# V1.net
KiCad netlist of a schematic drawn in EAGLE
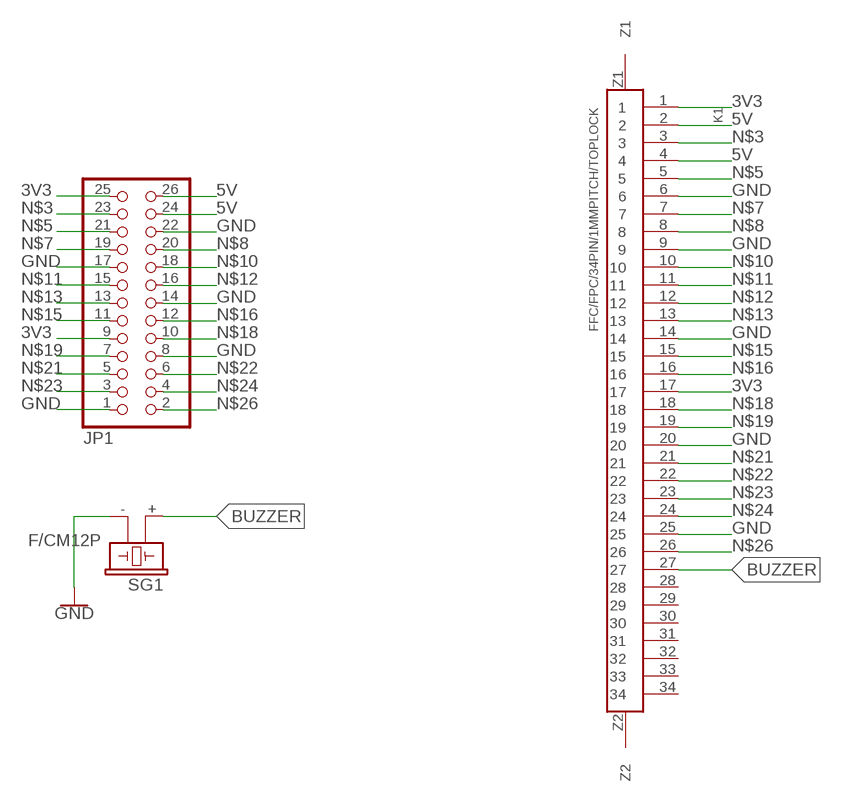
[diagram p0: schematic, sheet 1]

(export (version "E")
  (design (tool "Eeschema 10.0.6"))
  (components
    (comp (ref "JP1")
      (value "PINHD-2X13")
      (footprint "eagle-import:2X13")
      (libsource (lib "eagle-import") (part "PINHD-2X13"))
    )
    (comp (ref "K1")
      (value "FFC/FPC/34PIN/1MMPITCH/TOPLOCK")
      (footprint "eagle-import:FFC_FPC_34PIN_1MMPITCH_TOPLOCK")
      (libsource (lib "eagle-import") (part "FFC/FPC/34PIN/1MMPITCH/TOPLOCK"))
    )
    (comp (ref "SG1")
      (value "F/CM12P")
      (footprint "eagle-import:F_CM12P")
      (libsource (lib "eagle-import") (part "F/CM12P"))
    )
  )
  (nets
    (net (code "1") (name "/3V3") (class "Default")
      (node (ref "JP1") (pin "25") (pinfunction "25_25") (pintype "passive"))
      (node (ref "JP1") (pin "9") (pinfunction "9_9") (pintype "passive"))
      (node (ref "K1") (pin "1") (pinfunction "1_1") (pintype "bidirectional"))
      (node (ref "K1") (pin "17") (pinfunction "17_17") (pintype "bidirectional"))
    )
    (net (code "2") (name "/5V") (class "Default")
      (node (ref "JP1") (pin "24") (pinfunction "24_24") (pintype "passive"))
      (node (ref "JP1") (pin "26") (pinfunction "26_26") (pintype "passive"))
      (node (ref "K1") (pin "2") (pinfunction "2_2") (pintype "bidirectional"))
      (node (ref "K1") (pin "4") (pinfunction "4_4") (pintype "bidirectional"))
    )
    (net (code "3") (name "/N$3") (class "Default")
      (node (ref "JP1") (pin "23") (pinfunction "23_23") (pintype "passive"))
      (node (ref "K1") (pin "3") (pinfunction "3_3") (pintype "bidirectional"))
    )
    (net (code "4") (name "/N$5") (class "Default")
      (node (ref "JP1") (pin "21") (pinfunction "21_21") (pintype "passive"))
      (node (ref "K1") (pin "5") (pinfunction "5_5") (pintype "bidirectional"))
    )
    (net (code "5") (name "/N$7") (class "Default")
      (node (ref "JP1") (pin "19") (pinfunction "19_19") (pintype "passive"))
      (node (ref "K1") (pin "7") (pinfunction "7_7") (pintype "bidirectional"))
    )
    (net (code "6") (name "/N$8") (class "Default")
      (node (ref "JP1") (pin "20") (pinfunction "20_20") (pintype "passive"))
      (node (ref "K1") (pin "8") (pinfunction "8_8") (pintype "bidirectional"))
    )
    (net (code "7") (name "/N$10") (class "Default")
      (node (ref "JP1") (pin "18") (pinfunction "18_18") (pintype "passive"))
      (node (ref "K1") (pin "10") (pinfunction "10_10") (pintype "bidirectional"))
    )
    (net (code "8") (name "/N$11") (class "Default")
      (node (ref "JP1") (pin "15") (pinfunction "15_15") (pintype "passive"))
      (node (ref "K1") (pin "11") (pinfunction "11_11") (pintype "bidirectional"))
    )
    (net (code "9") (name "/N$12") (class "Default")
      (node (ref "JP1") (pin "16") (pinfunction "16_16") (pintype "passive"))
      (node (ref "K1") (pin "12") (pinfunction "12_12") (pintype "bidirectional"))
    )
    (net (code "10") (name "/N$13") (class "Default")
      (node (ref "JP1") (pin "13") (pinfunction "13_13") (pintype "passive"))
      (node (ref "K1") (pin "13") (pinfunction "13_13") (pintype "bidirectional"))
    )
    (net (code "11") (name "/N$15") (class "Default")
      (node (ref "JP1") (pin "11") (pinfunction "11_11") (pintype "passive"))
      (node (ref "K1") (pin "15") (pinfunction "15_15") (pintype "bidirectional"))
    )
    (net (code "12") (name "/N$16") (class "Default")
      (node (ref "JP1") (pin "12") (pinfunction "12_12") (pintype "passive"))
      (node (ref "K1") (pin "16") (pinfunction "16_16") (pintype "bidirectional"))
    )
    (net (code "13") (name "/N$18") (class "Default")
      (node (ref "JP1") (pin "10") (pinfunction "10_10") (pintype "passive"))
      (node (ref "K1") (pin "18") (pinfunction "18_18") (pintype "bidirectional"))
    )
    (net (code "14") (name "/N$19") (class "Default")
      (node (ref "JP1") (pin "7") (pinfunction "7_7") (pintype "passive"))
      (node (ref "K1") (pin "19") (pinfunction "19_19") (pintype "bidirectional"))
    )
    (net (code "15") (name "/N$21") (class "Default")
      (node (ref "JP1") (pin "5") (pinfunction "5_5") (pintype "passive"))
      (node (ref "K1") (pin "21") (pinfunction "21_21") (pintype "bidirectional"))
    )
    (net (code "16") (name "/N$22") (class "Default")
      (node (ref "JP1") (pin "6") (pinfunction "6_6") (pintype "passive"))
      (node (ref "K1") (pin "22") (pinfunction "22_22") (pintype "bidirectional"))
    )
    (net (code "17") (name "/N$23") (class "Default")
      (node (ref "JP1") (pin "3") (pinfunction "3_3") (pintype "passive"))
      (node (ref "K1") (pin "23") (pinfunction "23_23") (pintype "bidirectional"))
    )
    (net (code "18") (name "/N$24") (class "Default")
      (node (ref "JP1") (pin "4") (pinfunction "4_4") (pintype "passive"))
      (node (ref "K1") (pin "24") (pinfunction "24_24") (pintype "bidirectional"))
    )
    (net (code "19") (name "/N$26") (class "Default")
      (node (ref "JP1") (pin "2") (pinfunction "2_2") (pintype "passive"))
      (node (ref "K1") (pin "26") (pinfunction "26_26") (pintype "bidirectional"))
    )
    (net (code "20") (name "BUZZER") (class "Default")
      (node (ref "K1") (pin "27") (pinfunction "27_27") (pintype "bidirectional"))
      (node (ref "SG1") (pin "+") (pinfunction "1_+") (pintype "passive"))
    )
    (net (code "21") (name "GND") (class "Default")
      (node (ref "JP1") (pin "1") (pinfunction "1_1") (pintype "passive"))
      (node (ref "JP1") (pin "14") (pinfunction "14_14") (pintype "passive"))
      (node (ref "JP1") (pin "17") (pinfunction "17_17") (pintype "passive"))
      (node (ref "JP1") (pin "22") (pinfunction "22_22") (pintype "passive"))
      (node (ref "JP1") (pin "8") (pinfunction "8_8") (pintype "passive"))
      (node (ref "K1") (pin "14") (pinfunction "14_14") (pintype "bidirectional"))
      (node (ref "K1") (pin "20") (pinfunction "20_20") (pintype "bidirectional"))
      (node (ref "K1") (pin "25") (pinfunction "25_25") (pintype "bidirectional"))
      (node (ref "K1") (pin "6") (pinfunction "6_6") (pintype "bidirectional"))
      (node (ref "K1") (pin "9") (pinfunction "9_9") (pintype "bidirectional"))
      (node (ref "SG1") (pin "-") (pinfunction "2_-") (pintype "passive"))
    )
    (net (code "22") (name "unconnected-(K1-Pad28)") (class "Default")
      (node (ref "K1") (pin "28") (pinfunction "28_28") (pintype "bidirectional"))
    )
    (net (code "23") (name "unconnected-(K1-Pad29)") (class "Default")
      (node (ref "K1") (pin "29") (pinfunction "29_29") (pintype "bidirectional"))
    )
    (net (code "24") (name "unconnected-(K1-Pad30)") (class "Default")
      (node (ref "K1") (pin "30") (pinfunction "30_30") (pintype "bidirectional"))
    )
    (net (code "25") (name "unconnected-(K1-Pad31)") (class "Default")
      (node (ref "K1") (pin "31") (pinfunction "31_31") (pintype "bidirectional"))
    )
    (net (code "26") (name "unconnected-(K1-Pad32)") (class "Default")
      (node (ref "K1") (pin "32") (pinfunction "32_32") (pintype "bidirectional"))
    )
    (net (code "27") (name "unconnected-(K1-Pad33)") (class "Default")
      (node (ref "K1") (pin "33") (pinfunction "33_33") (pintype "bidirectional"))
    )
    (net (code "28") (name "unconnected-(K1-Pad34)") (class "Default")
      (node (ref "K1") (pin "34") (pinfunction "34_34") (pintype "bidirectional"))
    )
    (net (code "29") (name "unconnected-(K1-PadZ1)") (class "Default")
      (node (ref "K1") (pin "Z1") (pinfunction "Z1_Z1") (pintype "bidirectional"))
    )
    (net (code "30") (name "unconnected-(K1-PadZ2)") (class "Default")
      (node (ref "K1") (pin "Z2") (pinfunction "Z2_Z2") (pintype "bidirectional"))
    )
  )
)
